# CH32V407RET-R0.net
KiCad netlist of a schematic drawn in Altium Designer
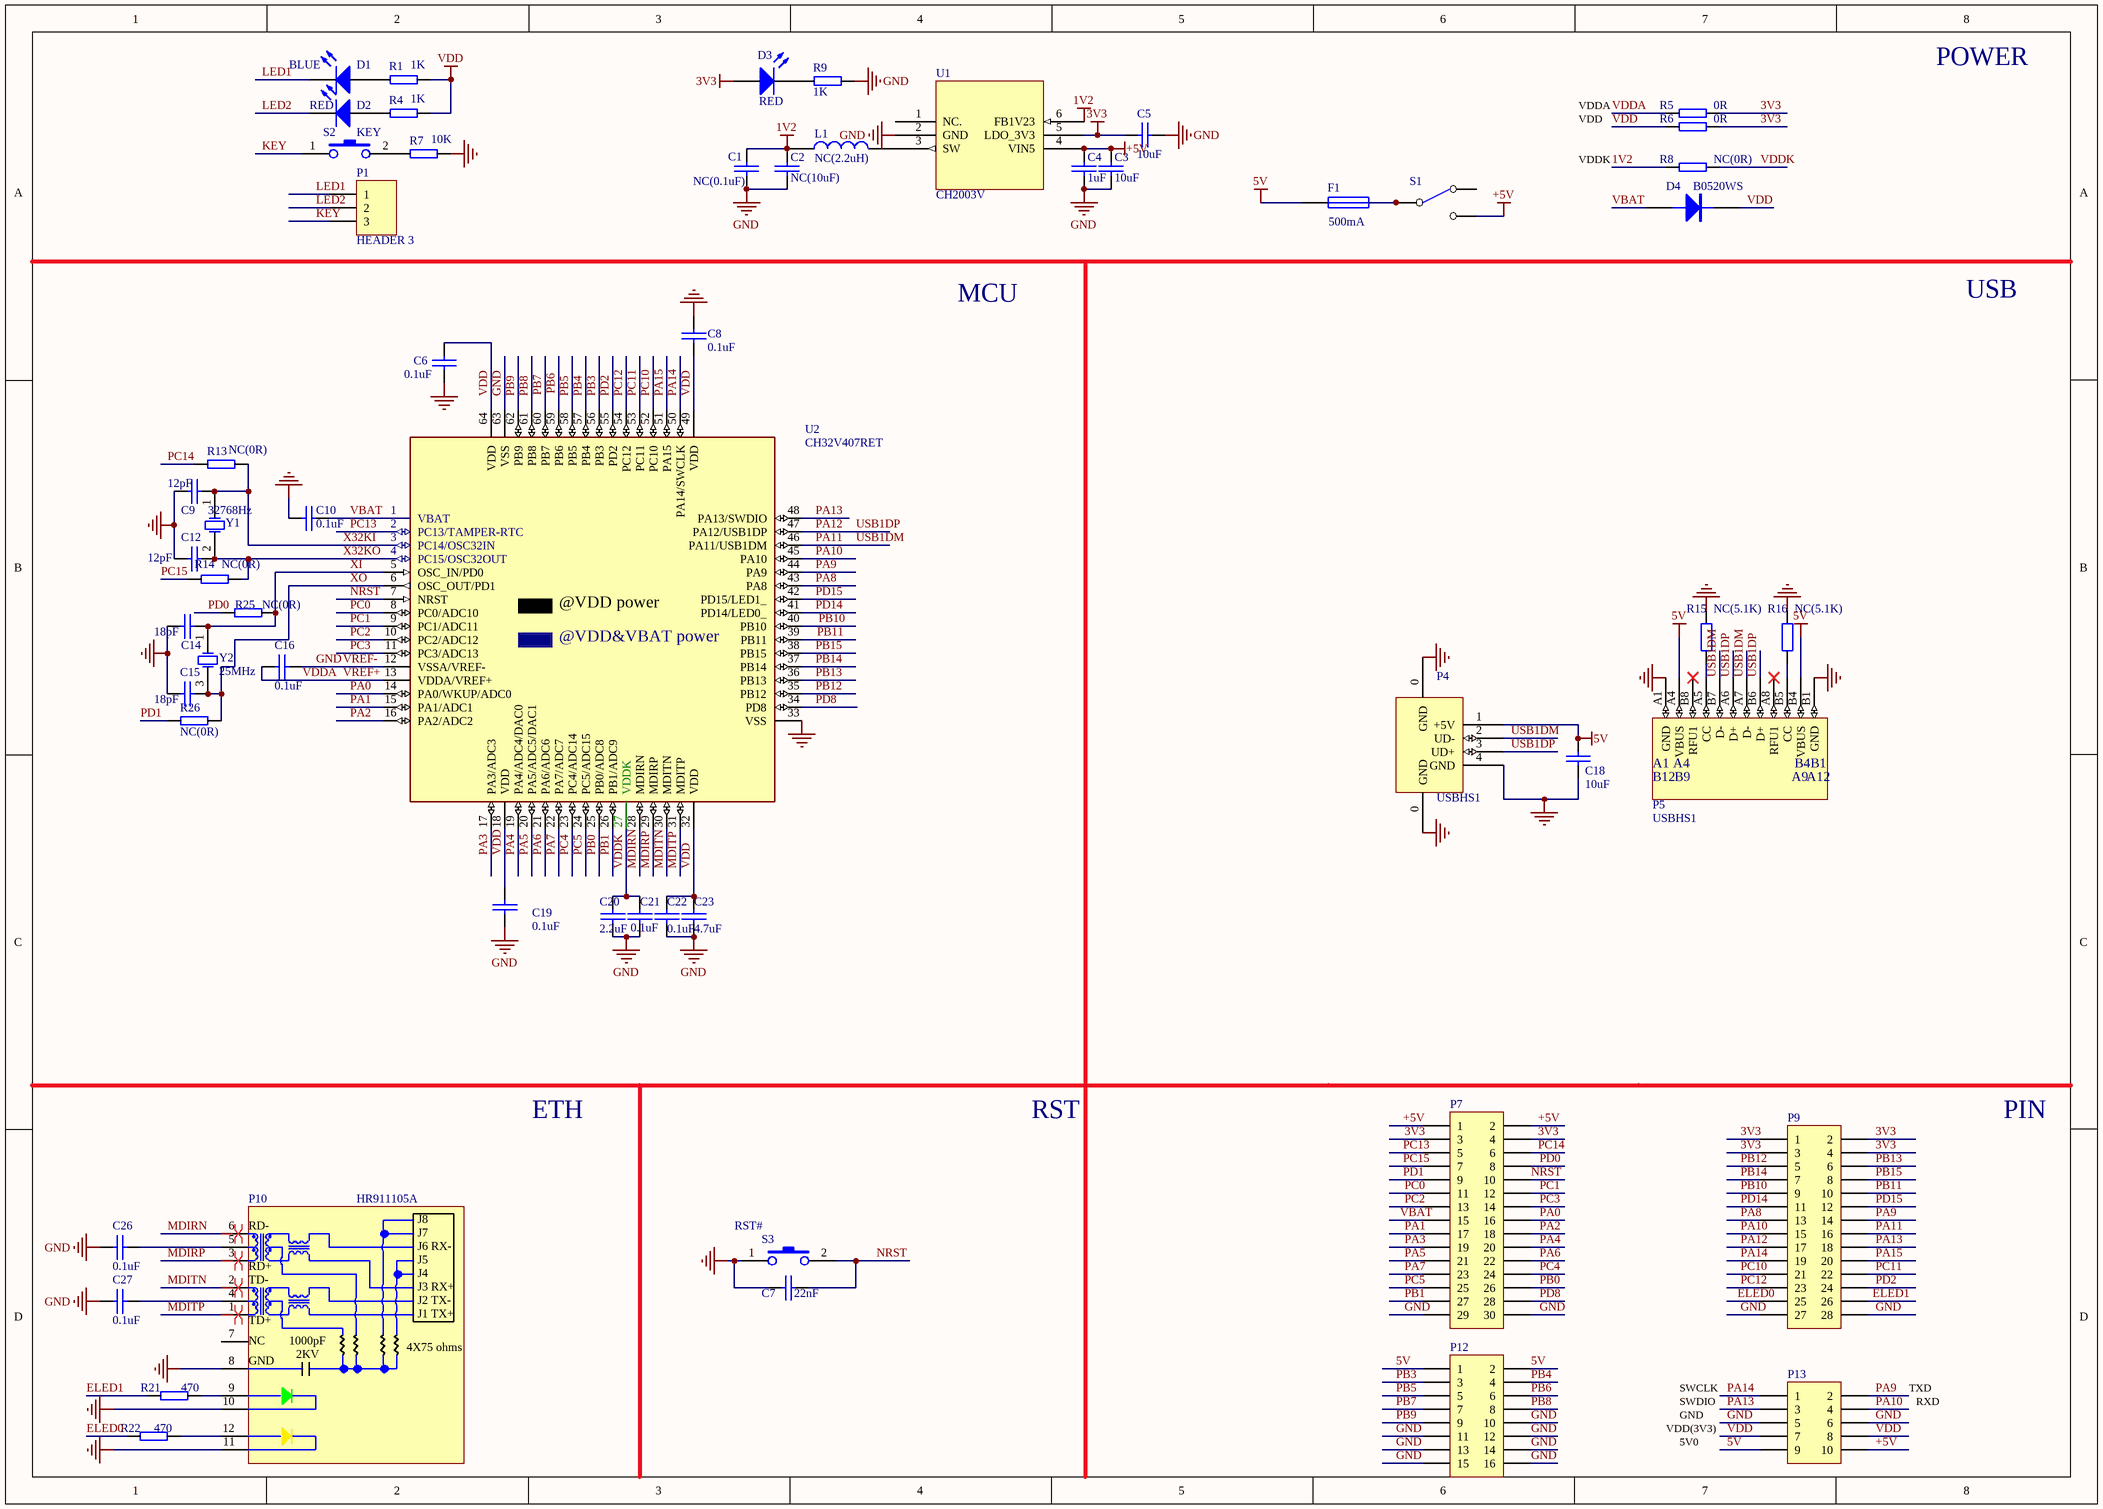
[diagram p0: CH32V407RET-R0.SchDoc]

(export (version "E")
  (design (tool "Eeschema 10.0.6"))
  (components
    (comp (ref "C1")
      (value "NC(0.1uF)")
      (footprint "0402_C")
      (description "Capacitor")
      (libsource (lib "") (part "CAP_1"))
    )
    (comp (ref "C2")
      (value "NC(10uF)")
      (footprint "0603_C")
      (description "Capacitor")
      (libsource (lib "*") (part "CAP"))
    )
    (comp (ref "C3")
      (value "10uF")
      (footprint "0603_C")
      (description "Capacitor")
      (libsource (lib "*") (part "CAP"))
    )
    (comp (ref "C4")
      (value "1uF")
      (footprint "0402_C")
      (description "Capacitor")
      (libsource (lib "") (part "CAP_1"))
    )
    (comp (ref "C5")
      (value "10uF")
      (footprint "0603_C")
      (description "Capacitor")
      (libsource (lib "*") (part "CAP"))
    )
    (comp (ref "C6")
      (value "0.1uF")
      (footprint "0402_C")
      (description "Capacitor")
      (libsource (lib "*") (part "CAP"))
    )
    (comp (ref "C7")
      (value "22nF")
      (footprint "0402_C")
      (description "Capacitor")
      (libsource (lib "") (part "CAP_2"))
    )
    (comp (ref "C8")
      (value "0.1uF")
      (footprint "0402_C")
      (description "Capacitor")
      (libsource (lib "*") (part "CAP"))
    )
    (comp (ref "C9")
      (value "12pF")
      (footprint "0402_C")
      (description "Capacitor")
      (libsource (lib "*") (part "CAP"))
    )
    (comp (ref "C10")
      (value "0.1uF")
      (footprint "0402_C")
      (description "Capacitor")
      (libsource (lib "*") (part "CAP"))
    )
    (comp (ref "C12")
      (value "12pF")
      (footprint "0402_C")
      (description "Capacitor")
      (libsource (lib "*") (part "CAP"))
    )
    (comp (ref "C14")
      (value "18pF")
      (footprint "0402_C")
      (description "Capacitor")
      (libsource (lib "*") (part "CAP"))
    )
    (comp (ref "C15")
      (value "18pF")
      (footprint "0402_C")
      (description "Capacitor")
      (libsource (lib "*") (part "CAP"))
    )
    (comp (ref "C16")
      (value "0.1uF")
      (footprint "0402_C")
      (description "Capacitor")
      (libsource (lib "*") (part "CAP"))
    )
    (comp (ref "C18")
      (value "10uF")
      (footprint "0603_C")
      (description "Capacitor")
      (libsource (lib "") (part "CAP_2"))
    )
    (comp (ref "C19")
      (value "0.1uF")
      (footprint "0402_C")
      (description "Capacitor")
      (libsource (lib "*") (part "CAP"))
    )
    (comp (ref "C20")
      (value "2.2uF")
      (footprint "0402_C")
      (description "Capacitor")
      (libsource (lib "*") (part "CAP"))
    )
    (comp (ref "C21")
      (value "0.1uF")
      (footprint "0402_C")
      (description "Capacitor")
      (libsource (lib "*") (part "CAP"))
    )
    (comp (ref "C22")
      (value "0.1uF")
      (footprint "0402_C")
      (description "Capacitor")
      (libsource (lib "*") (part "CAP"))
    )
    (comp (ref "C23")
      (value "4.7uF")
      (footprint "0402_C")
      (description "Capacitor")
      (libsource (lib "*") (part "CAP"))
    )
    (comp (ref "C26")
      (value "0.1uF")
      (footprint "0402_C")
      (description "Capacitor")
      (libsource (lib "wch_sch_others") (part "CAP"))
    )
    (comp (ref "C27")
      (value "0.1uF")
      (footprint "0402_C")
      (description "Capacitor")
      (libsource (lib "wch_sch_others") (part "CAP"))
    )
    (comp (ref "D1")
      (value "BLUE")
      (footprint "0603+")
      (description "Typical INFRARED GaAs LED")
      (fields (field (name "PUBLISHER") "Altium Limited"))
      (libsource (lib "*") (part "LED0"))
    )
    (comp (ref "D2")
      (value "RED")
      (footprint "0603+")
      (description "Typical INFRARED GaAs LED")
      (fields (field (name "PUBLISHER") "Altium Limited"))
      (libsource (lib "*") (part "LED0"))
    )
    (comp (ref "D3")
      (value "RED")
      (footprint "0603+")
      (description "Typical INFRARED GaAs LED")
      (fields (field (name "PUBLISHER") "Altium Limited"))
      (libsource (lib "*") (part "LED0"))
    )
    (comp (ref "D4")
      (value "B0520WS")
      (footprint "SOD-323")
      (description "Diode")
      (libsource (lib "*") (part "DIODE"))
    )
    (comp (ref "F1")
      (value "500mA")
      (footprint "0603")
      (description "Fuse")
      (libsource (lib "wch_sch_others") (part "FUSE1"))
    )
    (comp (ref "L1") (value "NC(2.2uH)") (footprint "CD32") (libsource (lib "*") (part "INDUCTOR")))
    (comp (ref "P1")
      (value "HEADER 3")
      (footprint "SIP3-2.54MM")
      (description "Header, 3-Pin")
      (libsource (lib "wch_sch_others") (part "HEADER 3"))
    )
    (comp (ref "P4")
      (value "USBHS1")
      (footprint "USBAF")
      (description "USB Port")
      (libsource (lib "*") (part "USB"))
    )
    (comp (ref "P5")
      (value "USBHS1")
      (footprint "TYPE-C-Receptacle-2.0")
      (libsource (lib "*") (part "TYPE-C1"))
    )
    (comp (ref "P7")
      (value "HEADER 15x2")
      (footprint "MYPCB:IDC30-2.54MM")
      (description "Header, 15-Pin, Dual row")
      (libsource (lib "wch_sch_others") (part "HEADER 15x2"))
    )
    (comp (ref "P9")
      (value "HEADER 14x2")
      (footprint "MYPCB:IDC28-2.54MM")
      (description "Header, 14-Pin, Dual row")
      (libsource (lib "wch_sch_others") (part "HEADER 14x2"))
    )
    (comp (ref "P10") (value "HR911105A") (footprint "HR911105A") (libsource (lib "*") (part "HR911105A")))
    (comp (ref "P12")
      (value "Ppin")
      (footprint "IDC16-2.54mm")
      (description "Header, 8-Pin, Dual row, Right Angle")
      (fields (field (name "PUBLISHER") "Altium Limited"))
      (libsource (lib "Miscellaneous Connectors") (part "Header 8X2H"))
    )
    (comp (ref "P13")
      (value "LINK")
      (footprint "IDC10-2.54mm")
      (description "Header, 5-Pin, Dual row, Right Angle")
      (fields (field (name "PUBLISHER") "Altium Limited"))
      (libsource (lib "Miscellaneous Connectors") (part "Header 5X2H"))
    )
    (comp (ref "R1") (value "1K") (footprint "0402") (libsource (lib "wch_sch_others") (part "RES")))
    (comp (ref "R4") (value "1K") (footprint "0402") (libsource (lib "wch_sch_others") (part "RES")))
    (comp (ref "R5") (value "0R") (footprint "0402") (libsource (lib "*") (part "R")))
    (comp (ref "R6") (value "0R") (footprint "0402") (libsource (lib "*") (part "R")))
    (comp (ref "R7") (value "10K") (footprint "0402") (libsource (lib "wch_sch_others") (part "RES")))
    (comp (ref "R8") (value "NC(0R)") (footprint "0402") (libsource (lib "*") (part "R")))
    (comp (ref "R9") (value "1K") (footprint "0402") (libsource (lib "wch_sch_others") (part "RES")))
    (comp (ref "R13") (value "NC(0R)") (footprint "0402") (libsource (lib "wch_sch_others") (part "RES")))
    (comp (ref "R14") (value "NC(0R)") (footprint "0402") (libsource (lib "wch_sch_others") (part "RES")))
    (comp (ref "R15")
      (value "NC(5.1K)")
      (footprint "0402")
      (description "Resistor")
      (libsource (lib "Miscellaneous Devices") (part "Res2"))
    )
    (comp (ref "R16")
      (value "NC(5.1K)")
      (footprint "0402")
      (description "Resistor")
      (libsource (lib "Miscellaneous Devices") (part "Res2"))
    )
    (comp (ref "R21") (value "470") (footprint "0402") (libsource (lib "wch_sch_others") (part "RES")))
    (comp (ref "R22") (value "470") (footprint "0402") (libsource (lib "wch_sch_others") (part "RES")))
    (comp (ref "R25") (value "NC(0R)") (footprint "0402") (libsource (lib "wch_sch_others") (part "RES")))
    (comp (ref "R26") (value "NC(0R)") (footprint "0402") (libsource (lib "wch_sch_others") (part "RES")))
    (comp (ref "S1") (value "SW SPDT") (footprint "SW1") (libsource (lib "*") (part "SW SPDT")))
    (comp (ref "S2")
      (value "KEY")
      (footprint "SMD_6.1x3.65x2.5mm-KEY")
      (libsource (lib "wch_sch_others") (part "KEY1"))
    )
    (comp (ref "S3")
      (value "RST#")
      (footprint "SMD_6.1x3.65x2.5mm-KEY")
      (libsource (lib "wch_sch_others") (part "KEY1"))
    )
    (comp (ref "U1")
      (value "CH2003V")
      (footprint "SOT-23-6")
      (description "Step-Down DC-DC Converter, 5V input, 1.23V * 800mA output, with LDO 3.3V * 200mA")
      (libsource (lib "CHXXX") (part "CH2003V"))
    )
    (comp (ref "U2")
      (value "CH32V407RET")
      (footprint "LQFP64_7X7")
      (description "RISC-V FPU HD-MCU, 175MHz, USB_480M, 100M Ethernet & Phy, CAN, ADC, DAC")
      (libsource (lib "DHXXXSCH") (part "CH32V407RET"))
    )
    (comp (ref "Y1")
      (value "32768Hz")
      (footprint "FC-135")
      (description "Crystal Oscillator")
      (fields (field (name "PUBLISHER") "Altium Limited"))
      (libsource (lib "*") (part "XTAL"))
    )
    (comp (ref "Y2")
      (value "25MHz")
      (footprint "XT3225")
      (description "Crystal Oscillator")
      (fields (field (name "PUBLISHER") "Altium Limited"))
      (libsource (lib "") (part "XTAL_1"))
    )
  )
  (nets
    (net (code "1") (name "+5V") (class "Default")
      (node (ref "C3") (pin "2") (pinfunction "2_2") (pintype "passive"))
      (node (ref "C4") (pin "2") (pinfunction "2_2") (pintype "passive"))
      (node (ref "P13") (pin "10") (pinfunction "10_10") (pintype "passive"))
      (node (ref "P7") (pin "1") (pinfunction "1_1") (pintype "passive"))
      (node (ref "P7") (pin "2") (pinfunction "2_2") (pintype "passive"))
      (node (ref "S1") (pin "2") (pinfunction "NC_2") (pintype "passive"))
      (node (ref "U1") (pin "4") (pinfunction "VIN5_4") (pintype "power_in"))
    )
    (net (code "3") (name "/ELED0") (class "Default")
      (node (ref "P9") (pin "25") (pinfunction "25_25") (pintype "passive"))
      (node (ref "R22") (pin "1") (pintype "passive"))
    )
    (net (code "4") (name "/ELED1") (class "Default")
      (node (ref "P9") (pin "26") (pinfunction "26_26") (pintype "passive"))
      (node (ref "R21") (pin "1") (pintype "passive"))
    )
    (net (code "5") (name "/KEY") (class "Default")
      (node (ref "P1") (pin "3") (pinfunction "3_3") (pintype "passive"))
      (node (ref "S2") (pin "1") (pinfunction "1_1") (pintype "passive"))
    )
    (net (code "6") (name "/LED1") (class "Default")
      (node (ref "D1") (pin "2") (pinfunction "K_2") (pintype "passive"))
      (node (ref "P1") (pin "1") (pinfunction "1_1") (pintype "passive"))
    )
    (net (code "7") (name "/LED2") (class "Default")
      (node (ref "D2") (pin "2") (pinfunction "K_2") (pintype "passive"))
      (node (ref "P1") (pin "2") (pinfunction "2_2") (pintype "passive"))
    )
    (net (code "8") (name "/MDIRN") (class "Default")
      (node (ref "P10") (pin "6") (pintype "passive"))
      (node (ref "U2") (pin "28") (pinfunction "MDIRN_28") (pintype "bidirectional"))
    )
    (net (code "9") (name "/MDIRP") (class "Default")
      (node (ref "P10") (pin "3") (pintype "passive"))
      (node (ref "U2") (pin "29") (pinfunction "MDIRP_29") (pintype "bidirectional"))
    )
    (net (code "10") (name "/MDITN") (class "Default")
      (node (ref "P10") (pin "2") (pintype "passive"))
      (node (ref "U2") (pin "30") (pinfunction "MDITN_30") (pintype "bidirectional"))
    )
    (net (code "11") (name "/MDITP") (class "Default")
      (node (ref "P10") (pin "1") (pintype "passive"))
      (node (ref "U2") (pin "31") (pinfunction "MDITP_31") (pintype "bidirectional"))
    )
    (net (code "12") (name "/NRST") (class "Default")
      (node (ref "C7") (pin "2") (pinfunction "2_2") (pintype "passive"))
      (node (ref "P7") (pin "10") (pinfunction "10_10") (pintype "passive"))
      (node (ref "S3") (pin "2") (pinfunction "2_2") (pintype "passive"))
      (node (ref "U2") (pin "7") (pinfunction "NRST_7") (pintype "input"))
    )
    (net (code "13") (name "/PA0") (class "Default")
      (node (ref "P7") (pin "16") (pinfunction "16_16") (pintype "passive"))
      (node (ref "U2") (pin "14") (pinfunction "PA0/WKUP/ADC0_14") (pintype "bidirectional"))
    )
    (net (code "14") (name "/PA1") (class "Default")
      (node (ref "P7") (pin "17") (pinfunction "17_17") (pintype "passive"))
      (node (ref "U2") (pin "15") (pinfunction "PA1/ADC1_15") (pintype "bidirectional"))
    )
    (net (code "15") (name "/PA2") (class "Default")
      (node (ref "P7") (pin "18") (pinfunction "18_18") (pintype "passive"))
      (node (ref "U2") (pin "16") (pinfunction "PA2/ADC2_16") (pintype "bidirectional"))
    )
    (net (code "16") (name "/PA3") (class "Default")
      (node (ref "P7") (pin "19") (pinfunction "19_19") (pintype "passive"))
      (node (ref "U2") (pin "17") (pinfunction "PA3/ADC3_17") (pintype "bidirectional"))
    )
    (net (code "17") (name "/PA4") (class "Default")
      (node (ref "P7") (pin "20") (pinfunction "20_20") (pintype "passive"))
      (node (ref "U2") (pin "19") (pinfunction "PA4/ADC4/DAC0_19") (pintype "bidirectional"))
    )
    (net (code "18") (name "/PA5") (class "Default")
      (node (ref "P7") (pin "21") (pinfunction "21_21") (pintype "passive"))
      (node (ref "U2") (pin "20") (pinfunction "PA5/ADC5/DAC1_20") (pintype "bidirectional"))
    )
    (net (code "19") (name "/PA6") (class "Default")
      (node (ref "P7") (pin "22") (pinfunction "22_22") (pintype "passive"))
      (node (ref "U2") (pin "21") (pinfunction "PA6/ADC6_21") (pintype "bidirectional"))
    )
    (net (code "20") (name "/PA7") (class "Default")
      (node (ref "P7") (pin "23") (pinfunction "23_23") (pintype "passive"))
      (node (ref "U2") (pin "22") (pinfunction "PA7/ADC7_22") (pintype "bidirectional"))
    )
    (net (code "21") (name "/PA8") (class "Default")
      (node (ref "P9") (pin "13") (pinfunction "13_13") (pintype "passive"))
      (node (ref "U2") (pin "43") (pinfunction "PA8_43") (pintype "bidirectional"))
    )
    (net (code "22") (name "/PA9") (class "Default")
      (node (ref "P13") (pin "2") (pinfunction "2_2") (pintype "passive"))
      (node (ref "P9") (pin "14") (pinfunction "14_14") (pintype "passive"))
      (node (ref "U2") (pin "44") (pinfunction "PA9_44") (pintype "bidirectional"))
    )
    (net (code "23") (name "/PA10") (class "Default")
      (node (ref "P13") (pin "4") (pinfunction "4_4") (pintype "passive"))
      (node (ref "P9") (pin "15") (pinfunction "15_15") (pintype "passive"))
      (node (ref "U2") (pin "45") (pinfunction "PA10_45") (pintype "bidirectional"))
    )
    (net (code "24") (name "/PA11") (class "Default")
      (node (ref "P4") (pin "2") (pinfunction "UD-_2") (pintype "bidirectional"))
      (node (ref "P5") (pin "A7") (pinfunction "D-_A7") (pintype "bidirectional"))
      (node (ref "P5") (pin "B7") (pinfunction "D-_B7") (pintype "bidirectional"))
      (node (ref "P9") (pin "16") (pinfunction "16_16") (pintype "passive"))
      (node (ref "U2") (pin "46") (pinfunction "PA11/USB1DM_46") (pintype "bidirectional"))
    )
    (net (code "25") (name "/PA12") (class "Default")
      (node (ref "P4") (pin "3") (pinfunction "UD+_3") (pintype "bidirectional"))
      (node (ref "P5") (pin "A6") (pinfunction "D+_A6") (pintype "bidirectional"))
      (node (ref "P5") (pin "B6") (pinfunction "D+_B6") (pintype "bidirectional"))
      (node (ref "P9") (pin "17") (pinfunction "17_17") (pintype "passive"))
      (node (ref "U2") (pin "47") (pinfunction "PA12/USB1DP_47") (pintype "bidirectional"))
    )
    (net (code "26") (name "/PA13") (class "Default")
      (node (ref "P13") (pin "3") (pinfunction "3_3") (pintype "passive"))
      (node (ref "P9") (pin "18") (pinfunction "18_18") (pintype "passive"))
      (node (ref "U2") (pin "48") (pinfunction "PA13/SWDIO_48") (pintype "bidirectional"))
    )
    (net (code "27") (name "/PA14") (class "Default")
      (node (ref "P13") (pin "1") (pinfunction "1_1") (pintype "passive"))
      (node (ref "P9") (pin "19") (pinfunction "19_19") (pintype "passive"))
      (node (ref "U2") (pin "50") (pinfunction "PA14/SWCLK_50") (pintype "bidirectional"))
    )
    (net (code "28") (name "/PA15") (class "Default")
      (node (ref "P9") (pin "20") (pinfunction "20_20") (pintype "passive"))
      (node (ref "U2") (pin "51") (pinfunction "PA15_51") (pintype "bidirectional"))
    )
    (net (code "29") (name "/PB0") (class "Default")
      (node (ref "P7") (pin "26") (pinfunction "26_26") (pintype "passive"))
      (node (ref "U2") (pin "25") (pinfunction "PB0/ADC8_25") (pintype "bidirectional"))
    )
    (net (code "30") (name "/PB1") (class "Default")
      (node (ref "P7") (pin "27") (pinfunction "27_27") (pintype "passive"))
      (node (ref "U2") (pin "26") (pinfunction "PB1/ADC9_26") (pintype "bidirectional"))
    )
    (net (code "31") (name "/PB3") (class "Default")
      (node (ref "P12") (pin "3") (pinfunction "3_3") (pintype "passive"))
      (node (ref "U2") (pin "56") (pinfunction "PB3_56") (pintype "bidirectional"))
    )
    (net (code "32") (name "/PB4") (class "Default")
      (node (ref "P12") (pin "4") (pinfunction "4_4") (pintype "passive"))
      (node (ref "U2") (pin "57") (pinfunction "PB4_57") (pintype "bidirectional"))
    )
    (net (code "33") (name "/PB5") (class "Default")
      (node (ref "P12") (pin "5") (pinfunction "5_5") (pintype "passive"))
      (node (ref "U2") (pin "58") (pinfunction "PB5_58") (pintype "bidirectional"))
    )
    (net (code "34") (name "/PB6") (class "Default")
      (node (ref "P12") (pin "6") (pinfunction "6_6") (pintype "passive"))
      (node (ref "U2") (pin "59") (pinfunction "PB6_59") (pintype "bidirectional"))
    )
    (net (code "35") (name "/PB7") (class "Default")
      (node (ref "P12") (pin "7") (pinfunction "7_7") (pintype "passive"))
      (node (ref "U2") (pin "60") (pinfunction "PB7_60") (pintype "bidirectional"))
    )
    (net (code "36") (name "/PB8") (class "Default")
      (node (ref "P12") (pin "8") (pinfunction "8_8") (pintype "passive"))
      (node (ref "U2") (pin "61") (pinfunction "PB8_61") (pintype "bidirectional"))
    )
    (net (code "37") (name "/PB9") (class "Default")
      (node (ref "P12") (pin "9") (pinfunction "9_9") (pintype "passive"))
      (node (ref "U2") (pin "62") (pinfunction "PB9_62") (pintype "bidirectional"))
    )
    (net (code "38") (name "/PB10") (class "Default")
      (node (ref "P9") (pin "9") (pinfunction "9_9") (pintype "passive"))
      (node (ref "U2") (pin "40") (pinfunction "PB10_40") (pintype "bidirectional"))
    )
    (net (code "39") (name "/PB11") (class "Default")
      (node (ref "P9") (pin "10") (pinfunction "10_10") (pintype "passive"))
      (node (ref "U2") (pin "39") (pinfunction "PB11_39") (pintype "bidirectional"))
    )
    (net (code "40") (name "/PB12") (class "Default")
      (node (ref "P9") (pin "5") (pinfunction "5_5") (pintype "passive"))
      (node (ref "U2") (pin "35") (pinfunction "PB12_35") (pintype "bidirectional"))
    )
    (net (code "41") (name "/PB13") (class "Default")
      (node (ref "P9") (pin "6") (pinfunction "6_6") (pintype "passive"))
      (node (ref "U2") (pin "36") (pinfunction "PB13_36") (pintype "bidirectional"))
    )
    (net (code "42") (name "/PB14") (class "Default")
      (node (ref "P9") (pin "7") (pinfunction "7_7") (pintype "passive"))
      (node (ref "U2") (pin "37") (pinfunction "PB14_37") (pintype "bidirectional"))
    )
    (net (code "43") (name "/PB15") (class "Default")
      (node (ref "P9") (pin "8") (pinfunction "8_8") (pintype "passive"))
      (node (ref "U2") (pin "38") (pinfunction "PB15_38") (pintype "bidirectional"))
    )
    (net (code "44") (name "/PC0") (class "Default")
      (node (ref "P7") (pin "11") (pinfunction "11_11") (pintype "passive"))
      (node (ref "U2") (pin "8") (pinfunction "PC0/ADC10_8") (pintype "bidirectional"))
    )
    (net (code "45") (name "/PC1") (class "Default")
      (node (ref "P7") (pin "12") (pinfunction "12_12") (pintype "passive"))
      (node (ref "U2") (pin "9") (pinfunction "PC1/ADC11_9") (pintype "bidirectional"))
    )
    (net (code "46") (name "/PC2") (class "Default")
      (node (ref "P7") (pin "13") (pinfunction "13_13") (pintype "passive"))
      (node (ref "U2") (pin "10") (pinfunction "PC2/ADC12_10") (pintype "bidirectional"))
    )
    (net (code "47") (name "/PC3") (class "Default")
      (node (ref "P7") (pin "14") (pinfunction "14_14") (pintype "passive"))
      (node (ref "U2") (pin "11") (pinfunction "PC3/ADC13_11") (pintype "bidirectional"))
    )
    (net (code "48") (name "/PC4") (class "Default")
      (node (ref "P7") (pin "24") (pinfunction "24_24") (pintype "passive"))
      (node (ref "U2") (pin "23") (pinfunction "PC4/ADC14_23") (pintype "bidirectional"))
    )
    (net (code "49") (name "/PC5") (class "Default")
      (node (ref "P7") (pin "25") (pinfunction "25_25") (pintype "passive"))
      (node (ref "U2") (pin "24") (pinfunction "PC5/ADC15_24") (pintype "bidirectional"))
    )
    (net (code "50") (name "/PC10") (class "Default")
      (node (ref "P9") (pin "21") (pinfunction "21_21") (pintype "passive"))
      (node (ref "U2") (pin "52") (pinfunction "PC10_52") (pintype "bidirectional"))
    )
    (net (code "51") (name "/PC11") (class "Default")
      (node (ref "P9") (pin "22") (pinfunction "22_22") (pintype "passive"))
      (node (ref "U2") (pin "53") (pinfunction "PC11_53") (pintype "bidirectional"))
    )
    (net (code "52") (name "/PC12") (class "Default")
      (node (ref "P9") (pin "23") (pinfunction "23_23") (pintype "passive"))
      (node (ref "U2") (pin "54") (pinfunction "PC12_54") (pintype "bidirectional"))
    )
    (net (code "53") (name "/PC13") (class "Default")
      (node (ref "P7") (pin "5") (pinfunction "5_5") (pintype "passive"))
      (node (ref "U2") (pin "2") (pinfunction "PC13/TAMPER-RTC_2") (pintype "bidirectional"))
    )
    (net (code "54") (name "/PC14") (class "Default")
      (node (ref "P7") (pin "6") (pinfunction "6_6") (pintype "passive"))
      (node (ref "R13") (pin "1") (pintype "passive"))
    )
    (net (code "55") (name "/PC15") (class "Default")
      (node (ref "P7") (pin "7") (pinfunction "7_7") (pintype "passive"))
      (node (ref "R14") (pin "1") (pintype "passive"))
    )
    (net (code "56") (name "/PD0") (class "Default")
      (node (ref "P7") (pin "8") (pinfunction "8_8") (pintype "passive"))
      (node (ref "R25") (pin "1") (pintype "passive"))
    )
    (net (code "57") (name "/PD1") (class "Default")
      (node (ref "P7") (pin "9") (pinfunction "9_9") (pintype "passive"))
      (node (ref "R26") (pin "2") (pintype "passive"))
    )
    (net (code "58") (name "/PD2") (class "Default")
      (node (ref "P9") (pin "24") (pinfunction "24_24") (pintype "passive"))
      (node (ref "U2") (pin "55") (pinfunction "PD2_55") (pintype "bidirectional"))
    )
    (net (code "59") (name "/PD8") (class "Default")
      (node (ref "P7") (pin "28") (pinfunction "28_28") (pintype "passive"))
      (node (ref "U2") (pin "34") (pinfunction "PD8_34") (pintype "bidirectional"))
    )
    (net (code "60") (name "/PD14") (class "Default")
      (node (ref "P9") (pin "11") (pinfunction "11_11") (pintype "passive"))
      (node (ref "U2") (pin "41") (pinfunction "PD14/LED0__41") (pintype "bidirectional"))
    )
    (net (code "61") (name "/PD15") (class "Default")
      (node (ref "P9") (pin "12") (pinfunction "12_12") (pintype "passive"))
      (node (ref "U2") (pin "42") (pinfunction "PD15/LED1__42") (pintype "bidirectional"))
    )
    (net (code "62") (name "/VBAT") (class "Default")
      (node (ref "C10") (pin "2") (pinfunction "2_2") (pintype "passive"))
      (node (ref "D4") (pin "1") (pinfunction "A_1") (pintype "passive"))
      (node (ref "P7") (pin "15") (pinfunction "15_15") (pintype "passive"))
      (node (ref "U2") (pin "1") (pinfunction "VBAT_1") (pintype "power_in"))
    )
    (net (code "63") (name "/VDDA") (class "Default")
      (node (ref "C16") (pin "1") (pinfunction "1_1") (pintype "passive"))
      (node (ref "R5") (pin "2") (pinfunction "2_2") (pintype "passive"))
      (node (ref "U2") (pin "13") (pinfunction "VDDA/VREF+_13") (pintype "power_in"))
    )
    (net (code "64") (name "/VDDK") (class "Default")
      (node (ref "C20") (pin "2") (pinfunction "2_2") (pintype "passive"))
      (node (ref "C21") (pin "2") (pinfunction "2_2") (pintype "passive"))
      (node (ref "R8") (pin "1") (pinfunction "1_1") (pintype "passive"))
      (node (ref "U2") (pin "27") (pinfunction "VDDK_27") (pintype "power_in"))
    )
    (net (code "65") (name "/X32KI") (class "Default")
      (node (ref "C9") (pin "2") (pinfunction "2_2") (pintype "passive"))
      (node (ref "R13") (pin "2") (pintype "passive"))
      (node (ref "U2") (pin "3") (pinfunction "PC14/OSC32IN_3") (pintype "bidirectional"))
      (node (ref "Y1") (pin "1") (pinfunction "OSC1_1") (pintype "passive"))
    )
    (net (code "66") (name "/X32KO") (class "Default")
      (node (ref "C12") (pin "2") (pinfunction "2_2") (pintype "passive"))
      (node (ref "R14") (pin "2") (pintype "passive"))
      (node (ref "U2") (pin "4") (pinfunction "PC15/OSC32OUT_4") (pintype "bidirectional"))
      (node (ref "Y1") (pin "2") (pinfunction "OSC2_2") (pintype "passive"))
    )
    (net (code "67") (name "/XI") (class "Default")
      (node (ref "C14") (pin "2") (pinfunction "2_2") (pintype "passive"))
      (node (ref "R25") (pin "2") (pintype "passive"))
      (node (ref "U2") (pin "5") (pinfunction "OSC_IN/PD0_5") (pintype "input"))
      (node (ref "Y2") (pin "1") (pinfunction "OSC1_1") (pintype "passive"))
    )
    (net (code "68") (name "/XO") (class "Default")
      (node (ref "C15") (pin "2") (pinfunction "2_2") (pintype "passive"))
      (node (ref "R26") (pin "1") (pintype "passive"))
      (node (ref "U2") (pin "6") (pinfunction "OSC_OUT/PD1_6") (pintype "output"))
      (node (ref "Y2") (pin "3") (pinfunction "OSC2_3") (pintype "passive"))
    )
    (net (code "69") (name "1V2") (class "Default")
      (node (ref "C1") (pin "2") (pinfunction "2_2") (pintype "passive"))
      (node (ref "C2") (pin "2") (pinfunction "2_2") (pintype "passive"))
      (node (ref "L1") (pin "2") (pinfunction "2_2") (pintype "passive"))
      (node (ref "R8") (pin "2") (pinfunction "2_2") (pintype "passive"))
      (node (ref "U1") (pin "6") (pinfunction "FB1V23_6") (pintype "input"))
    )
    (net (code "70") (name "3V3") (class "Default")
      (node (ref "C5") (pin "2") (pinfunction "2_2") (pintype "passive"))
      (node (ref "D3") (pin "1") (pinfunction "A_1") (pintype "passive"))
      (node (ref "P7") (pin "3") (pinfunction "3_3") (pintype "passive"))
      (node (ref "P7") (pin "4") (pinfunction "4_4") (pintype "passive"))
      (node (ref "P9") (pin "1") (pinfunction "1_1") (pintype "passive"))
      (node (ref "P9") (pin "2") (pinfunction "2_2") (pintype "passive"))
      (node (ref "P9") (pin "3") (pinfunction "3_3") (pintype "passive"))
      (node (ref "P9") (pin "4") (pinfunction "4_4") (pintype "passive"))
      (node (ref "R5") (pin "1") (pinfunction "1_1") (pintype "passive"))
      (node (ref "R6") (pin "1") (pinfunction "1_1") (pintype "passive"))
      (node (ref "U1") (pin "5") (pinfunction "LDO_3V3_5") (pintype "power_in"))
    )
    (net (code "71") (name "5V") (class "Default")
      (node (ref "C18") (pin "1") (pinfunction "1_1") (pintype "passive"))
      (node (ref "F1") (pin "1") (pinfunction "1_1") (pintype "passive"))
      (node (ref "P12") (pin "1") (pinfunction "1_1") (pintype "passive"))
      (node (ref "P12") (pin "2") (pinfunction "2_2") (pintype "passive"))
      (node (ref "P13") (pin "9") (pinfunction "9_9") (pintype "passive"))
      (node (ref "P4") (pin "1") (pinfunction "+5V_1") (pintype "power_in"))
      (node (ref "P5") (pin "A4") (pinfunction "VBUS_A4") (pintype "bidirectional"))
      (node (ref "P5") (pin "B4") (pinfunction "VBUS_B4") (pintype "bidirectional"))
    )
    (net (code "72") (name "GND") (class "Default")
      (node (ref "C1") (pin "1") (pinfunction "1_1") (pintype "passive"))
      (node (ref "C10") (pin "1") (pinfunction "1_1") (pintype "passive"))
      (node (ref "C12") (pin "1") (pinfunction "1_1") (pintype "passive"))
      (node (ref "C14") (pin "1") (pinfunction "1_1") (pintype "passive"))
      (node (ref "C15") (pin "1") (pinfunction "1_1") (pintype "passive"))
      (node (ref "C16") (pin "2") (pinfunction "2_2") (pintype "passive"))
      (node (ref "C18") (pin "2") (pinfunction "2_2") (pintype "passive"))
      (node (ref "C19") (pin "1") (pinfunction "1_1") (pintype "passive"))
      (node (ref "C2") (pin "1") (pinfunction "1_1") (pintype "passive"))
      (node (ref "C20") (pin "1") (pinfunction "1_1") (pintype "passive"))
      (node (ref "C21") (pin "1") (pinfunction "1_1") (pintype "passive"))
      (node (ref "C22") (pin "1") (pinfunction "1_1") (pintype "passive"))
      (node (ref "C23") (pin "1") (pinfunction "1_1") (pintype "passive"))
      (node (ref "C26") (pin "1") (pinfunction "1_1") (pintype "passive"))
      (node (ref "C27") (pin "1") (pinfunction "1_1") (pintype "passive"))
      (node (ref "C3") (pin "1") (pinfunction "1_1") (pintype "passive"))
      (node (ref "C4") (pin "1") (pinfunction "1_1") (pintype "passive"))
      (node (ref "C5") (pin "1") (pinfunction "1_1") (pintype "passive"))
      (node (ref "C6") (pin "1") (pinfunction "1_1") (pintype "passive"))
      (node (ref "C7") (pin "1") (pinfunction "1_1") (pintype "passive"))
      (node (ref "C8") (pin "2") (pinfunction "2_2") (pintype "passive"))
      (node (ref "C9") (pin "1") (pinfunction "1_1") (pintype "passive"))
      (node (ref "P10") (pin "10") (pintype "passive"))
      (node (ref "P10") (pin "11") (pintype "passive"))
      (node (ref "P10") (pin "8") (pintype "passive"))
      (node (ref "P12") (pin "10") (pinfunction "10_10") (pintype "passive"))
      (node (ref "P12") (pin "11") (pinfunction "11_11") (pintype "passive"))
      (node (ref "P12") (pin "12") (pinfunction "12_12") (pintype "passive"))
      (node (ref "P12") (pin "13") (pinfunction "13_13") (pintype "passive"))
      (node (ref "P12") (pin "14") (pinfunction "14_14") (pintype "passive"))
      (node (ref "P12") (pin "15") (pinfunction "15_15") (pintype "passive"))
      (node (ref "P12") (pin "16") (pinfunction "16_16") (pintype "passive"))
      (node (ref "P13") (pin "5") (pinfunction "5_5") (pintype "passive"))
      (node (ref "P13") (pin "6") (pinfunction "6_6") (pintype "passive"))
      (node (ref "P4") (pin "0") (pinfunction "GND_0") (pintype "power_in"))
      (node (ref "P4") (pin "4") (pinfunction "GND_4") (pintype "power_in"))
      (node (ref "P5") (pin "A1") (pinfunction "GND_A1") (pintype "bidirectional"))
      (node (ref "P5") (pin "B1") (pinfunction "GND_B1") (pintype "bidirectional"))
      (node (ref "P7") (pin "29") (pinfunction "29_29") (pintype "passive"))
      (node (ref "P7") (pin "30") (pinfunction "30_30") (pintype "passive"))
      (node (ref "P9") (pin "27") (pinfunction "27_27") (pintype "passive"))
      (node (ref "P9") (pin "28") (pinfunction "28_28") (pintype "passive"))
      (node (ref "R15") (pin "2") (pinfunction "2_2") (pintype "passive"))
      (node (ref "R16") (pin "2") (pinfunction "2_2") (pintype "passive"))
      (node (ref "R7") (pin "1") (pintype "passive"))
      (node (ref "R9") (pin "2") (pintype "passive"))
      (node (ref "S3") (pin "1") (pinfunction "1_1") (pintype "passive"))
      (node (ref "U1") (pin "2") (pinfunction "GND_2") (pintype "power_in"))
      (node (ref "U2") (pin "12") (pinfunction "VSSA/VREF-_12") (pintype "power_in"))
      (node (ref "U2") (pin "33") (pinfunction "VSS_33") (pintype "power_in"))
      (node (ref "U2") (pin "63") (pinfunction "VSS_63") (pintype "power_in"))
    )
    (net (code "73") (name "Net-(C26-Pad2)") (class "Default")
      (node (ref "C26") (pin "2") (pinfunction "2_2") (pintype "passive"))
      (node (ref "P10") (pin "5") (pintype "passive"))
    )
    (net (code "74") (name "Net-(C27-Pad2)") (class "Default")
      (node (ref "C27") (pin "2") (pinfunction "2_2") (pintype "passive"))
      (node (ref "P10") (pin "4") (pintype "passive"))
    )
    (net (code "75") (name "Net-(D1-A)") (class "Default")
      (node (ref "D1") (pin "1") (pinfunction "A_1") (pintype "passive"))
      (node (ref "R1") (pin "2") (pintype "passive"))
    )
    (net (code "76") (name "Net-(D2-A)") (class "Default")
      (node (ref "D2") (pin "1") (pinfunction "A_1") (pintype "passive"))
      (node (ref "R4") (pin "2") (pintype "passive"))
    )
    (net (code "77") (name "Net-(D3-K)") (class "Default")
      (node (ref "D3") (pin "2") (pinfunction "K_2") (pintype "passive"))
      (node (ref "R9") (pin "1") (pintype "passive"))
    )
    (net (code "78") (name "Net-(P5-CC-PadA5)") (class "Default")
      (node (ref "P5") (pin "A5") (pinfunction "CC_A5") (pintype "bidirectional"))
      (node (ref "R15") (pin "1") (pinfunction "1_1") (pintype "passive"))
    )
    (net (code "79") (name "Net-(P5-CC-PadB5)") (class "Default")
      (node (ref "P5") (pin "B5") (pinfunction "CC_B5") (pintype "bidirectional"))
      (node (ref "R16") (pin "1") (pinfunction "1_1") (pintype "passive"))
    )
    (net (code "80") (name "Net-(P10-Pad9)") (class "Default")
      (node (ref "P10") (pin "9") (pintype "passive"))
      (node (ref "R21") (pin "2") (pintype "passive"))
    )
    (net (code "81") (name "Net-(P10-Pad12)") (class "Default")
      (node (ref "P10") (pin "12") (pintype "passive"))
      (node (ref "R22") (pin "2") (pintype "passive"))
    )
    (net (code "82") (name "Net-(R7-Pad2)") (class "Default")
      (node (ref "R7") (pin "2") (pintype "passive"))
      (node (ref "S2") (pin "2") (pinfunction "2_2") (pintype "passive"))
    )
    (net (code "83") (name "Net-(S1-COMMON)") (class "Default")
      (node (ref "F1") (pin "2") (pinfunction "2_2") (pintype "passive"))
      (node (ref "S1") (pin "1") (pinfunction "COMMON_1") (pintype "passive"))
    )
    (net (code "84") (name "Net-(U1-SW)") (class "Default")
      (node (ref "L1") (pin "1") (pinfunction "1_1") (pintype "passive"))
      (node (ref "U1") (pin "3") (pinfunction "SW_3") (pintype "output"))
    )
    (net (code "85") (name "VDD") (class "Default")
      (node (ref "C19") (pin "2") (pinfunction "2_2") (pintype "passive"))
      (node (ref "C22") (pin "2") (pinfunction "2_2") (pintype "passive"))
      (node (ref "C23") (pin "2") (pinfunction "2_2") (pintype "passive"))
      (node (ref "C6") (pin "2") (pinfunction "2_2") (pintype "passive"))
      (node (ref "C8") (pin "1") (pinfunction "1_1") (pintype "passive"))
      (node (ref "D4") (pin "2") (pinfunction "K_2") (pintype "passive"))
      (node (ref "P13") (pin "7") (pinfunction "7_7") (pintype "passive"))
      (node (ref "P13") (pin "8") (pinfunction "8_8") (pintype "passive"))
      (node (ref "R1") (pin "1") (pintype "passive"))
      (node (ref "R4") (pin "1") (pintype "passive"))
      (node (ref "R6") (pin "2") (pinfunction "2_2") (pintype "passive"))
      (node (ref "U2") (pin "18") (pinfunction "VDD_18") (pintype "power_in"))
      (node (ref "U2") (pin "32") (pinfunction "VDD_32") (pintype "power_in"))
      (node (ref "U2") (pin "49") (pinfunction "VDD_49") (pintype "power_in"))
      (node (ref "U2") (pin "64") (pinfunction "VDD_64") (pintype "power_in"))
    )
    (net (code "86") (name "unconnected-(P5-RFU1-PadA8)") (class "Default")
      (node (ref "P5") (pin "A8") (pinfunction "RFU1_A8") (pintype "bidirectional+no_connect"))
    )
    (net (code "87") (name "unconnected-(P5-RFU1-PadB8)") (class "Default")
      (node (ref "P5") (pin "B8") (pinfunction "RFU1_B8") (pintype "bidirectional+no_connect"))
    )
    (net (code "88") (name "unconnected-(P10-Pad7)") (class "Default")
      (node (ref "P10") (pin "7") (pintype "passive"))
    )
    (net (code "89") (name "unconnected-(S1-NO-Pad3)") (class "Default")
      (node (ref "S1") (pin "3") (pinfunction "NO_3") (pintype "passive"))
    )
    (net (code "90") (name "unconnected-(U1-NC.-Pad1)") (class "Default")
      (node (ref "U1") (pin "1") (pinfunction "NC._1") (pintype "passive"))
    )
  )
)
